# ROL2-B1-P01.net
KiCad netlist of a schematic drawn in Altium Designer
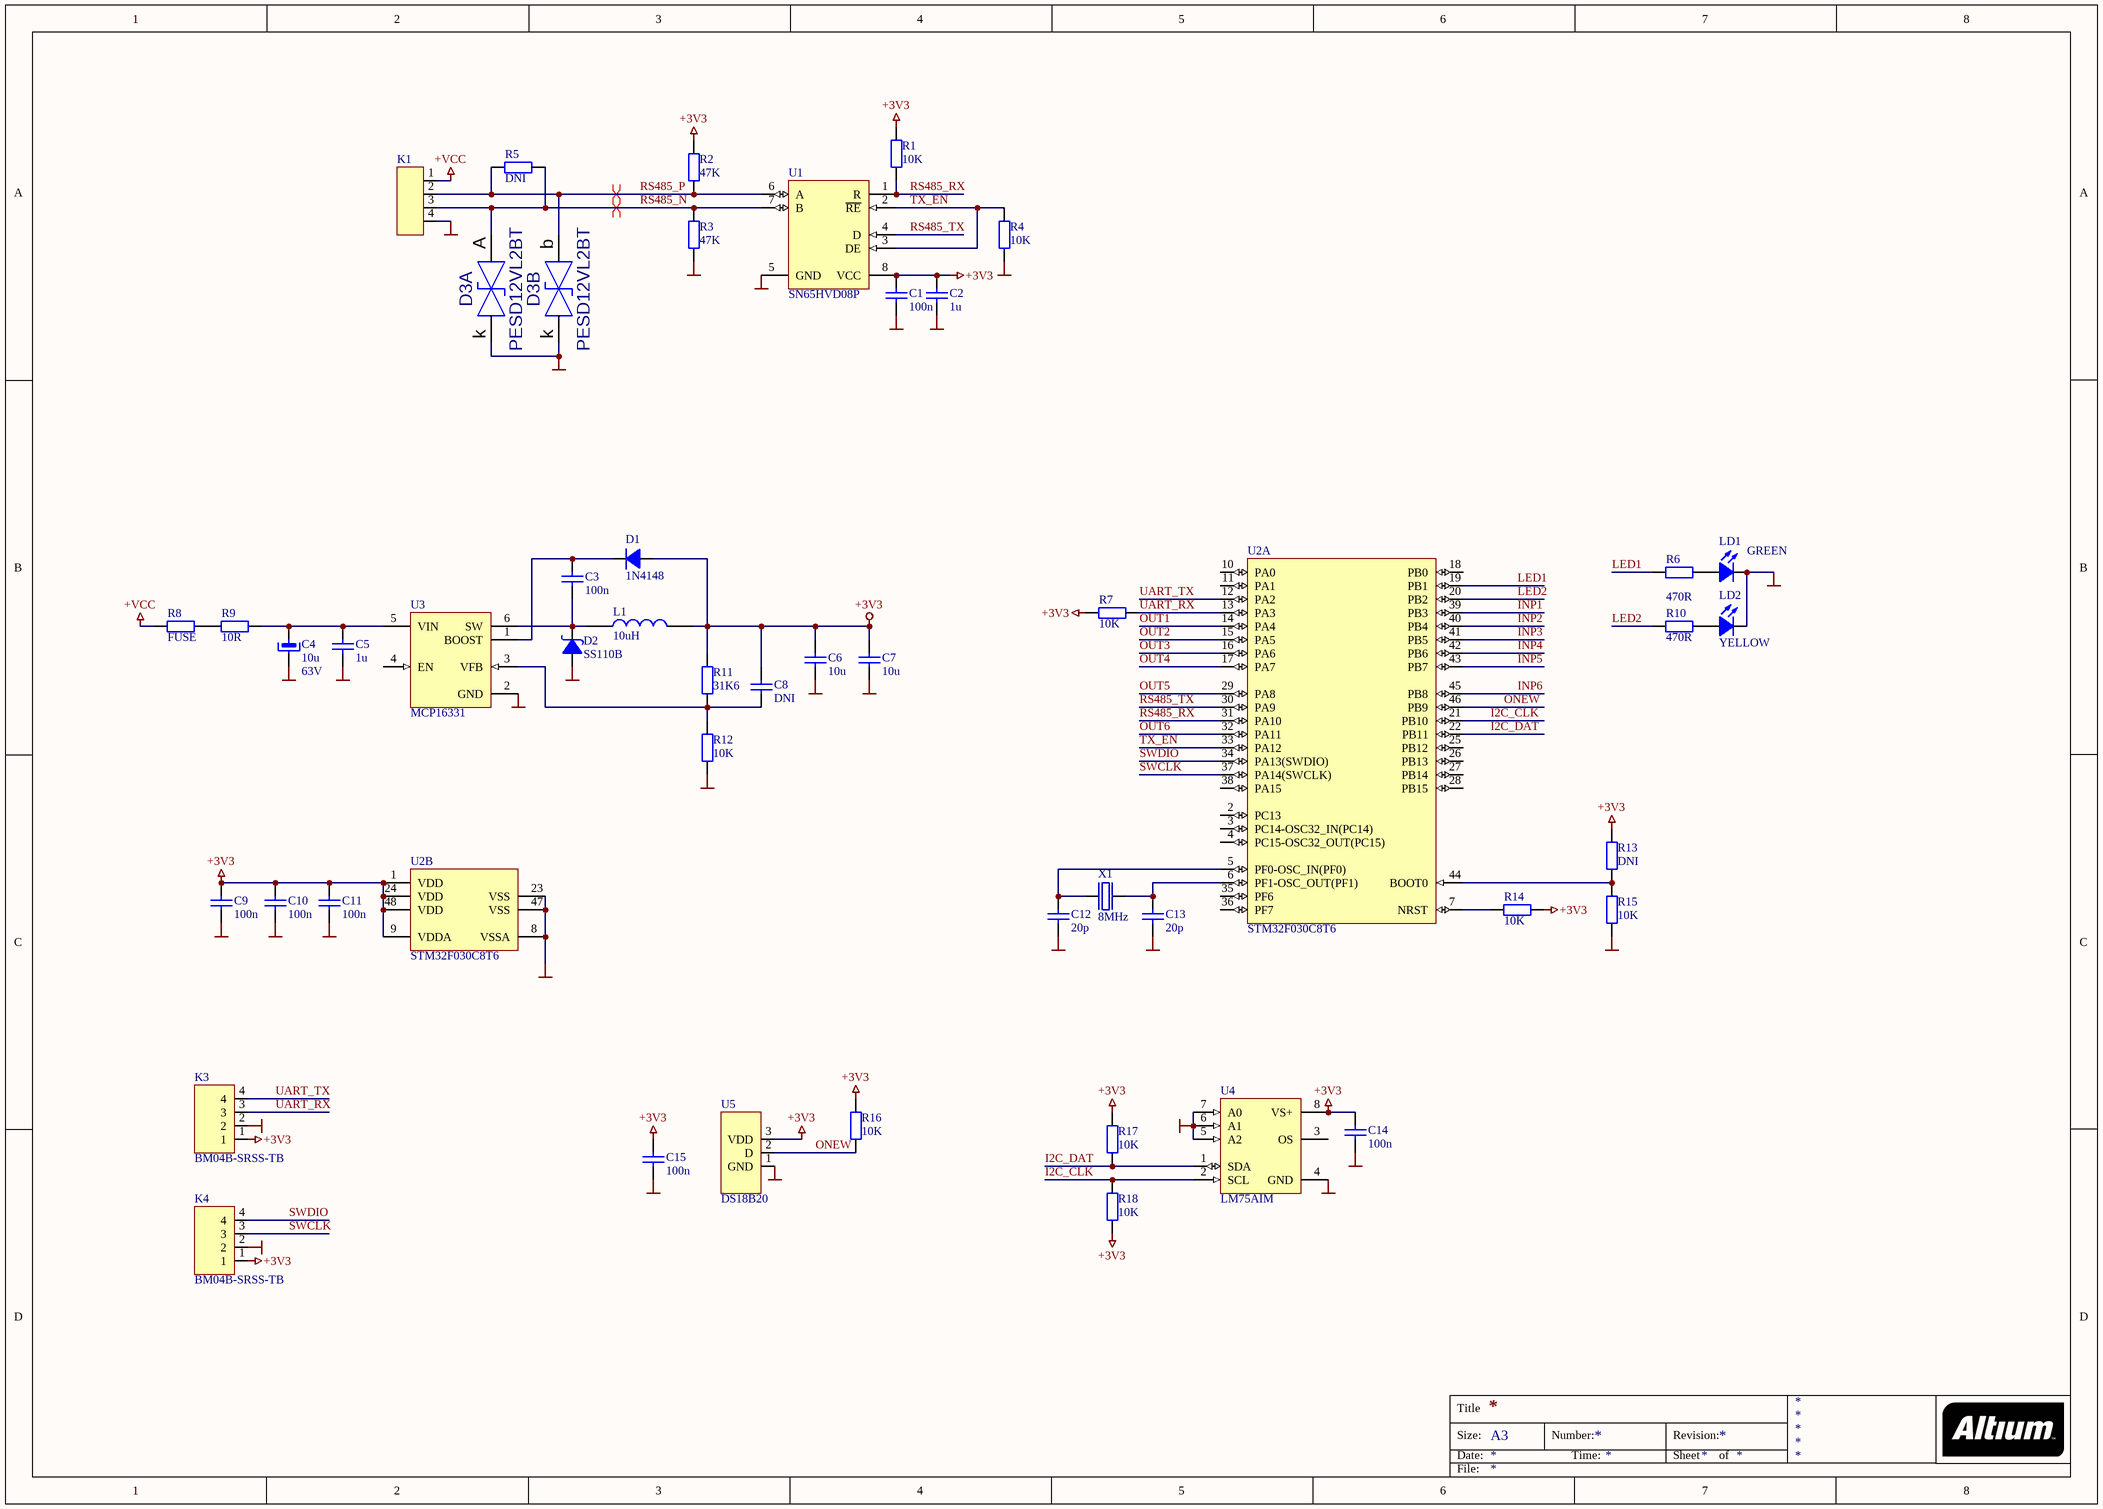
[diagram p0: ROL2-B1-P01.SchDoc]

(export (version "E")
  (design (tool "Eeschema 10.0.6"))
  (components
    (comp (ref "C1")
      (value "100n")
      (footprint "Passive:CC0805-1")
      (description "Capacitor chip ceramic 0805")
      (libsource (lib "CapChipCer") (part "CAPCC0805_1U50VX7R"))
    )
    (comp (ref "C2")
      (value "1u")
      (footprint "Passive:CC0805-1")
      (description "Capacitor chip ceramic 0805")
      (libsource (lib "CapChipCer") (part "CAPCC0805_1U50VX7R"))
    )
    (comp (ref "C3")
      (value "100n")
      (footprint "Passive:CC0805-1")
      (description "Capacitor chip ceramic 0805")
      (libsource (lib "CapChipCer") (part "CAPCC0805_1U50VX7R"))
    )
    (comp (ref "C4")
      (value "10u")
      (footprint "CAPPS-D6.3X7.7")
      (description "Capacitor electrolitic SMD 6.3X6.3X7.7MM low ESR")
      (fields (field (name "COMMENT2") "63V"))
      (libsource (lib "CapElectTht") (part "CAPPS100U25VFP"))
    )
    (comp (ref "C5")
      (value "1u")
      (footprint "Passive:CC0805-1")
      (description "Capacitor chip ceramic 0805")
      (libsource (lib "CapChipCer") (part "CAPCC0805_1U50VX7R"))
    )
    (comp (ref "C6")
      (value "10u")
      (footprint "CC0805-1")
      (description "Capacitor chip ceramic 0805")
      (libsource (lib "CapChipCer") (part "CAPCC0805_10U16VX5R"))
    )
    (comp (ref "C7")
      (value "10u")
      (footprint "CC0805-1")
      (description "Capacitor chip ceramic 0805")
      (libsource (lib "CapChipCer") (part "CAPCC0805_10U16VX5R"))
    )
    (comp (ref "C8")
      (value "DNI")
      (footprint "Passive:CC0805-1")
      (description "Capacitor chip ceramic 0805")
      (libsource (lib "CapChipCer") (part "CAPCC0805_1U50VX7R"))
    )
    (comp (ref "C9")
      (value "100n")
      (footprint "CC0805-1")
      (description "Capacitor chip ceramic 0805")
      (libsource (lib "CapChipCer") (part "CAPCC0805_100N50VX7R"))
    )
    (comp (ref "C10")
      (value "100n")
      (footprint "CC0805-1")
      (description "Capacitor chip ceramic 0805")
      (libsource (lib "CapChipCer") (part "CAPCC0805_100N50VX7R"))
    )
    (comp (ref "C11")
      (value "100n")
      (footprint "CC0805-1")
      (description "Capacitor chip ceramic 0805")
      (libsource (lib "CapChipCer") (part "CAPCC0805_100N50VX7R"))
    )
    (comp (ref "C12")
      (value "20p")
      (footprint "CC0805-1")
      (description "Capacitor chip ceramic 0805")
      (libsource (lib "CapChipCer") (part "CAPCC0805_100N50VX7R"))
    )
    (comp (ref "C13")
      (value "20p")
      (footprint "CC0805-1")
      (description "Capacitor chip ceramic 0805")
      (libsource (lib "CapChipCer") (part "CAPCC0805_100N50VX7R"))
    )
    (comp (ref "C14")
      (value "100n")
      (footprint "CC0805-1")
      (description "Capacitor chip ceramic 0805")
      (libsource (lib "CapChipCer") (part "CAPCC0805_100N50VX7R"))
    )
    (comp (ref "C15")
      (value "100n")
      (footprint "CC0805-1")
      (description "Capacitor chip ceramic 0805")
      (libsource (lib "CapChipCer") (part "CAPCC0805_100N50VX7R"))
    )
    (comp (ref "D1")
      (value "1N4148")
      (footprint "Active:SOD323")
      (description "Small Signal Diode")
      (fields (field (name "MANUFACTURER") "Vishay"))
      (libsource (lib "Discrete") (part "D-1N4148WS"))
    )
    (comp (ref "D2")
      (value "SS110B")
      (footprint "Passive:DO-214AC")
      (description "Schottky Diode")
      (fields (field (name "MANUFACTURER") "multicomp"))
      (libsource (lib "Discrete") (part "CD214A-B240LF-0.3V@1A"))
    )
    (comp (ref "D3")
      (value "PESD12VL2BT")
      (footprint "SOT-23_NUP2105L(Primary)")
      (description "Diode")
      (libsource (lib "fractal_lib") (part "NUP2105L"))
    )
    (comp (ref "K1")
      (value "Terminal Block Connector, 3.81mm, Right Angle")
      (footprint "CONN_3.81_4")
      (description "Terminal Block Connector, 3.81mm, 4pin")
      (libsource (lib "fractal_lib") (part "CONN_TB_3.81_4PIN"))
    )
    (comp (ref "K3")
      (value "BM04B-SRSS-TB")
      (footprint "JST-SH-4pin")
      (description "JST connector 4pin vertical")
      (libsource (lib "fractal_lib") (part "JST-SH-BM04B-SRSS-TB"))
    )
    (comp (ref "K4")
      (value "BM04B-SRSS-TB")
      (footprint "JST-SH-4pin")
      (description "JST connector 4pin vertical")
      (libsource (lib "fractal_lib") (part "JST-SH-BM04B-SRSS-TB"))
    )
    (comp (ref "L1")
      (value "10uH")
      (footprint "IND-LQH32CN4R7M33l")
      (description "Chip Inductor 4 x 4 mm")
      (fields (field (name "MANUFACTURER") "Murata"))
      (libsource (lib "Induct") (part "LQH44PN100MP0L"))
    )
    (comp (ref "LD1")
      (value "GREEN")
      (footprint "Active:LEDGREENC190")
      (description "LED green HSMG vertical")
      (fields (field (name "MANUFACTURER") "Avago"))
      (libsource (lib "Discrete") (part "LED-GREEN0603V"))
    )
    (comp (ref "LD2")
      (value "YELLOW")
      (footprint "Active:LEDYELLOWC190")
      (description "LED yellow HSMY vertical")
      (fields (field (name "MANUFACTURER") "Avago"))
      (libsource (lib "Discrete") (part "LED-YELLOW0603V"))
    )
    (comp (ref "R1")
      (value "10K")
      (footprint "RC0805-1")
      (description "Chip Resistor 0805")
      (libsource (lib "") (part "RES0805_1"))
    )
    (comp (ref "R2")
      (value "47K")
      (footprint "RC0805-1")
      (description "Chip Resistor 0805")
      (libsource (lib "Resistors") (part "RES0805"))
    )
    (comp (ref "R3")
      (value "47K")
      (footprint "RC0805-1")
      (description "Chip Resistor 0805")
      (libsource (lib "Resistors") (part "RES0805"))
    )
    (comp (ref "R4")
      (value "10K")
      (footprint "RC0805-1")
      (description "Chip Resistor 0805")
      (libsource (lib "") (part "RES0805_1"))
    )
    (comp (ref "R5")
      (value "DNI")
      (footprint "RC0805-1")
      (description "Chip Resistor 0805")
      (libsource (lib "") (part "RES0805_1"))
    )
    (comp (ref "R6")
      (value "470R")
      (footprint "RC0805-1")
      (description "Chip Resistor 0805")
      (libsource (lib "") (part "RES0805_1"))
    )
    (comp (ref "R7")
      (value "10K")
      (footprint "RC0805-1")
      (description "Chip Resistor 0805")
      (libsource (lib "") (part "RES0805_1"))
    )
    (comp (ref "R8")
      (value "FUSE")
      (footprint "RC1206-1")
      (description "Chip Resistor 1206")
      (libsource (lib "Resistors") (part "RES1206"))
    )
    (comp (ref "R9")
      (value "10R")
      (footprint "RC0805-1")
      (description "Chip Resistor 0805")
      (libsource (lib "") (part "RES0805_2"))
    )
    (comp (ref "R10")
      (value "470R")
      (footprint "RC0805-1")
      (description "Chip Resistor 0805")
      (libsource (lib "") (part "RES0805_1"))
    )
    (comp (ref "R11")
      (value "31K6")
      (footprint "RC0805-1")
      (description "Chip Resistor 0805")
      (libsource (lib "Resistors") (part "RES0805"))
    )
    (comp (ref "R12")
      (value "10K")
      (footprint "RC0805-1")
      (description "Chip Resistor 0805")
      (libsource (lib "Resistors") (part "RES0805"))
    )
    (comp (ref "R13")
      (value "DNI")
      (footprint "RC0805-1")
      (description "Chip Resistor 0805")
      (libsource (lib "Resistors") (part "RES0805"))
    )
    (comp (ref "R14")
      (value "10K")
      (footprint "RC0805-1")
      (description "Chip Resistor 0805")
      (libsource (lib "") (part "RES0805_2"))
    )
    (comp (ref "R15")
      (value "10K")
      (footprint "RC0805-1")
      (description "Chip Resistor 0805")
      (libsource (lib "") (part "RES0805_3"))
    )
    (comp (ref "R16")
      (value "10K")
      (footprint "RC0805-1")
      (description "Chip Resistor 0805")
      (libsource (lib "") (part "RES0805_3"))
    )
    (comp (ref "R17")
      (value "10K")
      (footprint "RC0805-1")
      (description "Chip Resistor 0805")
      (libsource (lib "") (part "RES0805_3"))
    )
    (comp (ref "R18")
      (value "10K")
      (footprint "RC0805-1")
      (description "Chip Resistor 0805")
      (libsource (lib "Resistors") (part "RES0805"))
    )
    (comp (ref "U1")
      (value "SN65HVD08P")
      (footprint "M08A_L")
      (description "3.3 / 5 V RS-485 Transceiver, 10 Mbps, Half Duplex, -40 to 85 degC, 8-pin PDIP (P), Pb-Free (RoHS)")
      (fields (field (name "MANUFACTURER") "Texas Instruments"))
      (libsource (lib "fractal_lib") (part "SN65HVD08P"))
    )
    (comp (ref "U2")
      (value "STM32F030C8T6")
      (footprint "STM-LQFP48_N")
      (libsource (lib "fractal_lib") (part "STM32F030C8T6"))
    )
    (comp (ref "U3")
      (value "MCP16331")
      (footprint "MCHP-SOT-23-CH6_N")
      (fields (field (name "MANUFACTURER") "Microchip") (field (name "PARTNUMBER") "MCP16301T-E/CH"))
      (libsource (lib "fractal_lib") (part "MCP16301T-E/CH"))
    )
    (comp (ref "U4")
      (value "LM75AIM")
      (footprint "M08A_N")
      (description "Digital Temperature Sensor and Thermal Watchdog with Two-Wire Interface, 8-pin Narrow SOIC")
      (fields (field (name "MANUFACTURER") "National Semiconductor"))
      (libsource (lib "fractal_lib") (part "LM75AIM"))
    )
    (comp (ref "U5")
      (value "DS18B20")
      (footprint "TO92")
      (description "digital temperature sensor")
      (libsource (lib "fractal_lib") (part "DS18B20"))
    )
    (comp (ref "X1")
      (value "8MHz")
      (footprint "OSCCC150X320X9-2N")
      (description "SMD Crystal 8MHz")
      (libsource (lib "fractal_lib") (part "XTAL-SMD_8MHz"))
    )
  )
  (nets
    (net (code "1") (name "+3V3") (class "Default")
      (node (ref "C1") (pin "2") (pinfunction "2_2") (pintype "passive"))
      (node (ref "C10") (pin "2") (pinfunction "2_2") (pintype "passive"))
      (node (ref "C11") (pin "2") (pinfunction "2_2") (pintype "passive"))
      (node (ref "C14") (pin "2") (pinfunction "2_2") (pintype "passive"))
      (node (ref "C15") (pin "2") (pinfunction "2_2") (pintype "passive"))
      (node (ref "C2") (pin "2") (pinfunction "2_2") (pintype "passive"))
      (node (ref "C6") (pin "2") (pinfunction "2_2") (pintype "passive"))
      (node (ref "C7") (pin "2") (pinfunction "2_2") (pintype "passive"))
      (node (ref "C8") (pin "2") (pinfunction "2_2") (pintype "passive"))
      (node (ref "C9") (pin "2") (pinfunction "2_2") (pintype "passive"))
      (node (ref "D1") (pin "2") (pinfunction "A_2") (pintype "passive"))
      (node (ref "K3") (pin "1") (pinfunction "1_1") (pintype "passive"))
      (node (ref "K4") (pin "1") (pinfunction "1_1") (pintype "passive"))
      (node (ref "L1") (pin "2") (pinfunction "2_2") (pintype "passive"))
      (node (ref "R1") (pin "2") (pinfunction "2_2") (pintype "passive"))
      (node (ref "R11") (pin "2") (pinfunction "2_2") (pintype "passive"))
      (node (ref "R13") (pin "2") (pinfunction "2_2") (pintype "passive"))
      (node (ref "R14") (pin "1") (pinfunction "1_1") (pintype "passive"))
      (node (ref "R16") (pin "1") (pinfunction "1_1") (pintype "passive"))
      (node (ref "R17") (pin "1") (pinfunction "1_1") (pintype "passive"))
      (node (ref "R18") (pin "1") (pinfunction "1_1") (pintype "passive"))
      (node (ref "R2") (pin "2") (pinfunction "2_2") (pintype "passive"))
      (node (ref "R7") (pin "1") (pinfunction "1_1") (pintype "passive"))
      (node (ref "U1") (pin "8") (pinfunction "VCC_8") (pintype "power_in"))
      (node (ref "U2") (pin "1") (pinfunction "VDD_1") (pintype "power_in"))
      (node (ref "U2") (pin "24") (pinfunction "VDD_24") (pintype "power_in"))
      (node (ref "U2") (pin "48") (pinfunction "VDD_48") (pintype "power_in"))
      (node (ref "U2") (pin "9") (pinfunction "VDDA_9") (pintype "power_in"))
      (node (ref "U4") (pin "8") (pinfunction "VS+_8") (pintype "power_in"))
      (node (ref "U5") (pin "3") (pinfunction "VDD_3") (pintype "passive"))
    )
    (net (code "2") (name "+VCC") (class "Default")
      (node (ref "K1") (pin "1") (pinfunction "A_1") (pintype "passive"))
      (node (ref "R8") (pin "1") (pinfunction "1_1") (pintype "passive"))
    )
    (net (code "3") (name "/I2C_CLK") (class "Default")
      (node (ref "R18") (pin "2") (pinfunction "2_2") (pintype "passive"))
      (node (ref "U2") (pin "21") (pinfunction "PB10_21") (pintype "bidirectional"))
      (node (ref "U4") (pin "2") (pinfunction "SCL_2") (pintype "input"))
    )
    (net (code "4") (name "/I2C_DAT") (class "Default")
      (node (ref "R17") (pin "2") (pinfunction "2_2") (pintype "passive"))
      (node (ref "U2") (pin "22") (pinfunction "PB11_22") (pintype "bidirectional"))
      (node (ref "U4") (pin "1") (pinfunction "SDA_1") (pintype "bidirectional"))
    )
    (net (code "5") (name "/INP1") (class "Default")
      (node (ref "U2") (pin "39") (pinfunction "PB3_39") (pintype "bidirectional"))
    )
    (net (code "6") (name "/INP2") (class "Default")
      (node (ref "U2") (pin "40") (pinfunction "PB4_40") (pintype "bidirectional"))
    )
    (net (code "7") (name "/INP3") (class "Default")
      (node (ref "U2") (pin "41") (pinfunction "PB5_41") (pintype "bidirectional"))
    )
    (net (code "8") (name "/INP4") (class "Default")
      (node (ref "U2") (pin "42") (pinfunction "PB6_42") (pintype "bidirectional"))
    )
    (net (code "9") (name "/INP5") (class "Default")
      (node (ref "U2") (pin "43") (pinfunction "PB7_43") (pintype "bidirectional"))
    )
    (net (code "10") (name "/INP6") (class "Default")
      (node (ref "U2") (pin "45") (pinfunction "PB8_45") (pintype "bidirectional"))
    )
    (net (code "11") (name "/LED1") (class "Default")
      (node (ref "R6") (pin "1") (pinfunction "1_1") (pintype "passive"))
      (node (ref "U2") (pin "19") (pinfunction "PB1_19") (pintype "bidirectional"))
    )
    (net (code "12") (name "/LED2") (class "Default")
      (node (ref "R10") (pin "1") (pinfunction "1_1") (pintype "passive"))
      (node (ref "U2") (pin "20") (pinfunction "PB2_20") (pintype "bidirectional"))
    )
    (net (code "13") (name "/ONEW") (class "Default")
      (node (ref "R16") (pin "2") (pinfunction "2_2") (pintype "passive"))
      (node (ref "U2") (pin "46") (pinfunction "PB9_46") (pintype "bidirectional"))
      (node (ref "U5") (pin "2") (pinfunction "D_2") (pintype "passive"))
    )
    (net (code "14") (name "/OUT1") (class "Default")
      (node (ref "U2") (pin "14") (pinfunction "PA4_14") (pintype "bidirectional"))
    )
    (net (code "15") (name "/OUT2") (class "Default")
      (node (ref "U2") (pin "15") (pinfunction "PA5_15") (pintype "bidirectional"))
    )
    (net (code "16") (name "/OUT3") (class "Default")
      (node (ref "U2") (pin "16") (pinfunction "PA6_16") (pintype "bidirectional"))
    )
    (net (code "17") (name "/OUT4") (class "Default")
      (node (ref "U2") (pin "17") (pinfunction "PA7_17") (pintype "bidirectional"))
    )
    (net (code "18") (name "/OUT5") (class "Default")
      (node (ref "U2") (pin "29") (pinfunction "PA8_29") (pintype "bidirectional"))
    )
    (net (code "19") (name "/OUT6") (class "Default")
      (node (ref "U2") (pin "32") (pinfunction "PA11_32") (pintype "bidirectional"))
    )
    (net (code "20") (name "/RS485_N") (class "Default")
      (node (ref "D3") (pin "A") (pinfunction "A_A") (pintype "passive"))
      (node (ref "K1") (pin "3") (pinfunction "A_3") (pintype "passive"))
      (node (ref "R3") (pin "2") (pinfunction "2_2") (pintype "passive"))
      (node (ref "R5") (pin "2") (pinfunction "2_2") (pintype "passive"))
      (node (ref "U1") (pin "7") (pinfunction "B_7") (pintype "bidirectional"))
    )
    (net (code "21") (name "/RS485_P") (class "Default")
      (node (ref "D3") (pin "b") (pinfunction "A_b") (pintype "passive"))
      (node (ref "K1") (pin "2") (pinfunction "K_2") (pintype "passive"))
      (node (ref "R2") (pin "1") (pinfunction "1_1") (pintype "passive"))
      (node (ref "R5") (pin "1") (pinfunction "1_1") (pintype "passive"))
      (node (ref "U1") (pin "6") (pinfunction "A_6") (pintype "bidirectional"))
    )
    (net (code "22") (name "/RS485_RX") (class "Default")
      (node (ref "R1") (pin "1") (pinfunction "1_1") (pintype "passive"))
      (node (ref "U1") (pin "1") (pinfunction "R_1") (pintype "tri_state"))
      (node (ref "U2") (pin "31") (pinfunction "PA10_31") (pintype "bidirectional"))
    )
    (net (code "23") (name "/RS485_TX") (class "Default")
      (node (ref "U1") (pin "4") (pinfunction "D_4") (pintype "input"))
      (node (ref "U2") (pin "30") (pinfunction "PA9_30") (pintype "bidirectional"))
    )
    (net (code "24") (name "/SWCLK") (class "Default")
      (node (ref "K4") (pin "3") (pinfunction "3_3") (pintype "passive"))
      (node (ref "U2") (pin "37") (pinfunction "PA14(SWCLK)_37") (pintype "bidirectional"))
    )
    (net (code "25") (name "/SWDIO") (class "Default")
      (node (ref "K4") (pin "4") (pinfunction "4_4") (pintype "passive"))
      (node (ref "U2") (pin "34") (pinfunction "PA13(SWDIO)_34") (pintype "bidirectional"))
    )
    (net (code "26") (name "/TX_EN") (class "Default")
      (node (ref "R4") (pin "2") (pinfunction "2_2") (pintype "passive"))
      (node (ref "U1") (pin "2") (pinfunction "~{RE}_2") (pintype "input"))
      (node (ref "U1") (pin "3") (pinfunction "DE_3") (pintype "input"))
      (node (ref "U2") (pin "33") (pinfunction "PA12_33") (pintype "bidirectional"))
    )
    (net (code "27") (name "/UART_RX") (class "Default")
      (node (ref "K3") (pin "3") (pinfunction "3_3") (pintype "passive"))
      (node (ref "R7") (pin "2") (pinfunction "2_2") (pintype "passive"))
      (node (ref "U2") (pin "13") (pinfunction "PA3_13") (pintype "bidirectional"))
    )
    (net (code "28") (name "/UART_TX") (class "Default")
      (node (ref "K3") (pin "4") (pinfunction "4_4") (pintype "passive"))
      (node (ref "U2") (pin "12") (pinfunction "PA2_12") (pintype "bidirectional"))
    )
    (net (code "29") (name "GND") (class "Default")
      (node (ref "C1") (pin "1") (pinfunction "1_1") (pintype "passive"))
      (node (ref "C10") (pin "1") (pinfunction "1_1") (pintype "passive"))
      (node (ref "C11") (pin "1") (pinfunction "1_1") (pintype "passive"))
      (node (ref "C12") (pin "1") (pinfunction "1_1") (pintype "passive"))
      (node (ref "C13") (pin "1") (pinfunction "1_1") (pintype "passive"))
      (node (ref "C14") (pin "1") (pinfunction "1_1") (pintype "passive"))
      (node (ref "C15") (pin "1") (pinfunction "1_1") (pintype "passive"))
      (node (ref "C2") (pin "1") (pinfunction "1_1") (pintype "passive"))
      (node (ref "C4") (pin "2") (pinfunction "2_2") (pintype "passive"))
      (node (ref "C5") (pin "1") (pinfunction "1_1") (pintype "passive"))
      (node (ref "C6") (pin "1") (pinfunction "1_1") (pintype "passive"))
      (node (ref "C7") (pin "1") (pinfunction "1_1") (pintype "passive"))
      (node (ref "C9") (pin "1") (pinfunction "1_1") (pintype "passive"))
      (node (ref "D2") (pin "A") (pinfunction "A_A") (pintype "passive"))
      (node (ref "D3") (pin "k") (pinfunction "K_k") (pintype "power_in"))
      (node (ref "K1") (pin "4") (pinfunction "K_4") (pintype "passive"))
      (node (ref "K3") (pin "2") (pinfunction "2_2") (pintype "passive"))
      (node (ref "K4") (pin "2") (pinfunction "2_2") (pintype "passive"))
      (node (ref "LD1") (pin "1") (pinfunction "C_1") (pintype "passive"))
      (node (ref "LD2") (pin "1") (pinfunction "C_1") (pintype "passive"))
      (node (ref "R12") (pin "1") (pinfunction "1_1") (pintype "passive"))
      (node (ref "R15") (pin "2") (pinfunction "2_2") (pintype "passive"))
      (node (ref "R3") (pin "1") (pinfunction "1_1") (pintype "passive"))
      (node (ref "R4") (pin "1") (pinfunction "1_1") (pintype "passive"))
      (node (ref "U1") (pin "5") (pinfunction "GND_5") (pintype "power_in"))
      (node (ref "U2") (pin "23") (pinfunction "VSS_23") (pintype "power_in"))
      (node (ref "U2") (pin "47") (pinfunction "VSS_47") (pintype "power_in"))
      (node (ref "U2") (pin "8") (pinfunction "VSSA_8") (pintype "power_in"))
      (node (ref "U3") (pin "2") (pinfunction "GND_2") (pintype "power_in"))
      (node (ref "U4") (pin "4") (pinfunction "GND_4") (pintype "power_in"))
      (node (ref "U4") (pin "5") (pinfunction "A2_5") (pintype "input"))
      (node (ref "U4") (pin "6") (pinfunction "A1_6") (pintype "input"))
      (node (ref "U4") (pin "7") (pinfunction "A0_7") (pintype "input"))
      (node (ref "U5") (pin "1") (pinfunction "GND_1") (pintype "passive"))
    )
    (net (code "30") (name "Net-(D1-C)") (class "Default")
      (node (ref "C3") (pin "2") (pinfunction "2_2") (pintype "passive"))
      (node (ref "D1") (pin "1") (pinfunction "C_1") (pintype "passive"))
      (node (ref "U3") (pin "1") (pinfunction "BOOST_1") (pintype "power_in"))
    )
    (net (code "31") (name "Net-(LD1-A)") (class "Default")
      (node (ref "LD1") (pin "2") (pinfunction "A_2") (pintype "passive"))
      (node (ref "R6") (pin "2") (pinfunction "2_2") (pintype "passive"))
    )
    (net (code "32") (name "Net-(LD2-A)") (class "Default")
      (node (ref "LD2") (pin "2") (pinfunction "A_2") (pintype "passive"))
      (node (ref "R10") (pin "2") (pinfunction "2_2") (pintype "passive"))
    )
    (net (code "33") (name "Net-(R8-Pad2)") (class "Default")
      (node (ref "R8") (pin "2") (pinfunction "2_2") (pintype "passive"))
      (node (ref "R9") (pin "2") (pinfunction "2_2") (pintype "passive"))
    )
    (net (code "34") (name "Net-(U2A-BOOT0)") (class "Default")
      (node (ref "R13") (pin "1") (pinfunction "1_1") (pintype "passive"))
      (node (ref "R15") (pin "1") (pinfunction "1_1") (pintype "passive"))
      (node (ref "U2") (pin "44") (pinfunction "BOOT0_44") (pintype "input"))
    )
    (net (code "35") (name "Net-(U2A-NRST)") (class "Default")
      (node (ref "R14") (pin "2") (pinfunction "2_2") (pintype "passive"))
      (node (ref "U2") (pin "7") (pinfunction "NRST_7") (pintype "bidirectional"))
    )
    (net (code "36") (name "Net-(U2A-PF0-OSC_IN(PF0))") (class "Default")
      (node (ref "C12") (pin "2") (pinfunction "2_2") (pintype "passive"))
      (node (ref "U2") (pin "5") (pinfunction "PF0-OSC_IN(PF0)_5") (pintype "bidirectional"))
      (node (ref "X1") (pin "1") (pinfunction "OUT_1") (pintype "power_in"))
    )
    (net (code "37") (name "Net-(U2A-PF1-OSC_OUT(PF1))") (class "Default")
      (node (ref "C13") (pin "2") (pinfunction "2_2") (pintype "passive"))
      (node (ref "U2") (pin "6") (pinfunction "PF1-OSC_OUT(PF1)_6") (pintype "bidirectional"))
      (node (ref "X1") (pin "2") (pinfunction "IN_2") (pintype "passive"))
    )
    (net (code "38") (name "Net-(U3-SW)") (class "Default")
      (node (ref "C3") (pin "1") (pinfunction "1_1") (pintype "passive"))
      (node (ref "D2") (pin "K") (pinfunction "K_K") (pintype "passive"))
      (node (ref "L1") (pin "1") (pinfunction "1_1") (pintype "passive"))
      (node (ref "U3") (pin "6") (pinfunction "SW_6") (pintype "power_in"))
    )
    (net (code "39") (name "Net-(U3-VFB)") (class "Default")
      (node (ref "C8") (pin "1") (pinfunction "1_1") (pintype "passive"))
      (node (ref "R11") (pin "1") (pinfunction "1_1") (pintype "passive"))
      (node (ref "R12") (pin "2") (pinfunction "2_2") (pintype "passive"))
      (node (ref "U3") (pin "3") (pinfunction "VFB_3") (pintype "input"))
    )
    (net (code "40") (name "Net-(U3-VIN)") (class "Default")
      (node (ref "C4") (pin "1") (pinfunction "1_1") (pintype "passive"))
      (node (ref "C5") (pin "2") (pinfunction "2_2") (pintype "passive"))
      (node (ref "R9") (pin "1") (pinfunction "1_1") (pintype "passive"))
      (node (ref "U3") (pin "5") (pinfunction "VIN_5") (pintype "power_in"))
    )
    (net (code "41") (name "unconnected-(U2A-PA0-Pad10)") (class "Default")
      (node (ref "U2") (pin "10") (pinfunction "PA0_10") (pintype "bidirectional"))
    )
    (net (code "42") (name "unconnected-(U2A-PA1-Pad11)") (class "Default")
      (node (ref "U2") (pin "11") (pinfunction "PA1_11") (pintype "bidirectional"))
    )
    (net (code "43") (name "unconnected-(U2A-PA15-Pad38)") (class "Default")
      (node (ref "U2") (pin "38") (pinfunction "PA15_38") (pintype "bidirectional"))
    )
    (net (code "44") (name "unconnected-(U2A-PB0-Pad18)") (class "Default")
      (node (ref "U2") (pin "18") (pinfunction "PB0_18") (pintype "bidirectional"))
    )
    (net (code "45") (name "unconnected-(U2A-PB12-Pad25)") (class "Default")
      (node (ref "U2") (pin "25") (pinfunction "PB12_25") (pintype "bidirectional"))
    )
    (net (code "46") (name "unconnected-(U2A-PB13-Pad26)") (class "Default")
      (node (ref "U2") (pin "26") (pinfunction "PB13_26") (pintype "bidirectional"))
    )
    (net (code "47") (name "unconnected-(U2A-PB14-Pad27)") (class "Default")
      (node (ref "U2") (pin "27") (pinfunction "PB14_27") (pintype "bidirectional"))
    )
    (net (code "48") (name "unconnected-(U2A-PB15-Pad28)") (class "Default")
      (node (ref "U2") (pin "28") (pinfunction "PB15_28") (pintype "bidirectional"))
    )
    (net (code "49") (name "unconnected-(U2A-PC13-Pad2)") (class "Default")
      (node (ref "U2") (pin "2") (pinfunction "PC13_2") (pintype "bidirectional"))
    )
    (net (code "50") (name "unconnected-(U2A-PC14-OSC32_IN(PC14)-Pad3)") (class "Default")
      (node (ref "U2") (pin "3") (pinfunction "PC14-OSC32_IN(PC14)_3") (pintype "bidirectional"))
    )
    (net (code "51") (name "unconnected-(U2A-PC15-OSC32_OUT(PC15)-Pad4)") (class "Default")
      (node (ref "U2") (pin "4") (pinfunction "PC15-OSC32_OUT(PC15)_4") (pintype "bidirectional"))
    )
    (net (code "52") (name "unconnected-(U2A-PF6-Pad35)") (class "Default")
      (node (ref "U2") (pin "35") (pinfunction "PF6_35") (pintype "bidirectional"))
    )
    (net (code "53") (name "unconnected-(U2A-PF7-Pad36)") (class "Default")
      (node (ref "U2") (pin "36") (pinfunction "PF7_36") (pintype "bidirectional"))
    )
    (net (code "54") (name "unconnected-(U3-EN-Pad4)") (class "Default")
      (node (ref "U3") (pin "4") (pinfunction "EN_4") (pintype "input"))
    )
    (net (code "55") (name "unconnected-(U4-OS-Pad3)") (class "Default")
      (node (ref "U4") (pin "3") (pinfunction "OS_3") (pintype "open_collector"))
    )
  )
)
